# PowerSupply.net
KiCad netlist of a schematic drawn in Altium Designer
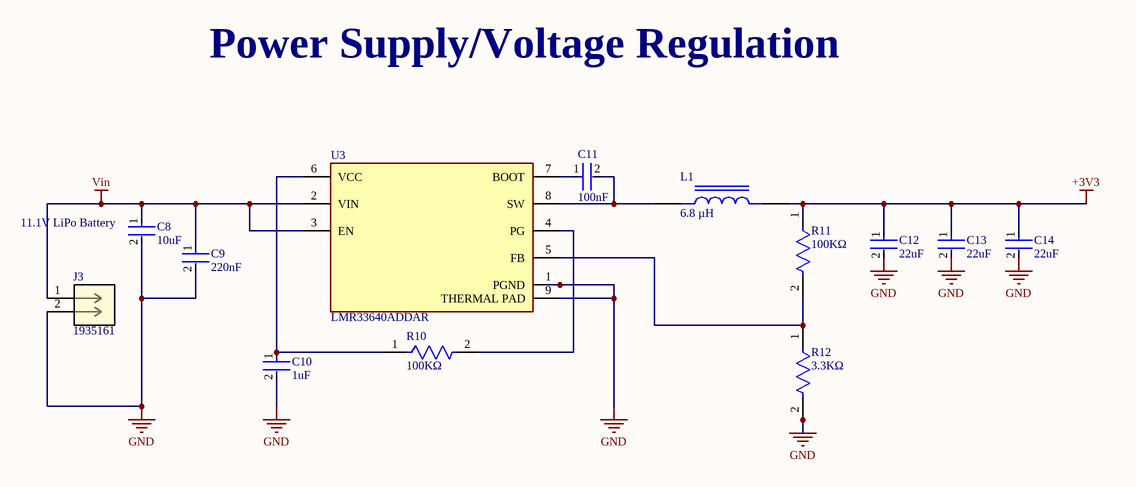
[diagram p0: PowerSupply.SchDoc]

(export (version "E")
  (design (tool "Eeschema 10.0.6"))
  (components
    (comp (ref "C8")
      (value "10uF")
      (footprint "FP-CL21-IPC_A")
      (description "CL21A106KAYNNNE CL21 Series 0805 10uF 25V ±10% Tolerance X5R Multilayer Ceramic Chip Capacitor")
      (fields (field (name "TOLERANCE") "10%"))
      (libsource (lib "Altium Content Vault") (part "b4654b650e69147ec39a6b967a45e02"))
    )
    (comp (ref "C9")
      (value "220nF")
      (footprint "FP-CL21-IPC_B")
      (description "CL21B224KAFNNNE CL21 Series 0805 220nF 25V ±10% Tolerance X7R Multilayer Ceramic Chip Capacitor")
      (fields (field (name "TOLERANCE") "10%"))
      (libsource (lib "Altium Content Vault") (part "b4654b650e69147ec39a6b967a45e02"))
    )
    (comp (ref "C10")
      (value "1uF")
      (footprint "FP-CL10-IPC_C")
      (description "CL10A105KA8NNNC Cap Ceramic 1uF 25V X5R ±10% Pad SMD 0603 +85°C T/R")
      (fields (field (name "VOLTAGE") "25V") (field (name "TOLERANCE") "10%"))
      (libsource (lib "Altium Content Vault") (part "b4654b650e69147ec39a6b967a45e02"))
    )
    (comp (ref "C11")
      (value "100nF")
      (footprint "FP-CL21-IPC_C")
      (description "CL21B104KACNNNC CL21 Series 0805 100nF 25V ±10% Tolerance X7R Multilayer Ceramic Chip Capacitor")
      (fields (field (name "VOLTAGE") "25V") (field (name "TOLERANCE") "10%"))
      (libsource (lib "Altium Content Vault") (part "b4654b650e69147ec39a6b967a45e02"))
    )
    (comp (ref "C12")
      (value "22uF")
      (footprint "FP-CL21-IPC_C")
      (description "CL21A226MAYNNNE CL21 Series 0805 22uF 25V ±20% Tolerance X5R Multilayer Ceramic Chip Capacitor")
      (libsource (lib "Altium Content Vault") (part "b4654b650e69147ec39a6b967a45e02"))
    )
    (comp (ref "C13")
      (value "22uF")
      (footprint "FP-CL21-IPC_C")
      (description "CL21A226MAYNNNE CL21 Series 0805 22uF 25V ±20% Tolerance X5R Multilayer Ceramic Chip Capacitor")
      (libsource (lib "Altium Content Vault") (part "b4654b650e69147ec39a6b967a45e02"))
    )
    (comp (ref "C14")
      (value "22uF")
      (footprint "FP-CL21-IPC_C")
      (description "CL21A226MAYNNNE CL21 Series 0805 22uF 25V ±20% Tolerance X5R Multilayer Ceramic Chip Capacitor")
      (libsource (lib "Altium Content Vault") (part "b4654b650e69147ec39a6b967a45e02"))
    )
    (comp (ref "J3")
      (value "1935161")
      (footprint "CONN_1935161_PXC")
      (fields
        (field (name "MANUFACTURER") "Samsung")
        (field (name "MANUFACTURER PART NUMBER") "CL21A106KOQNNNE")
      )
      (libsource (lib "1935161") (part "1935161"))
    )
    (comp (ref "L1")
      (value "6.8 µH")
      (footprint "IND_SRN8040TA-6R8M:IND_SRN8040TA-6R8M")
      (description "SRN8040TA-6R8M FIXED IND 6.8UH 5.1A 25 MOHM SMD")
      (fields (field (name "MP") "SRN8040TA-6R8M"))
      (libsource (lib "SRN8040TA-6R8M") (part "SRN8040TA-6R8M"))
    )
    (comp (ref "R10")
      (value "100KΩ")
      (footprint "FP-CRGP2512-IPC_C")
      (description "CRGP2512F100K CRGP2512 100KΩ 2W ±100ppm/°C 1% 500V")
      (fields
        (field (name "OCTOPART") "https://octopart.com/crgp2512f100k-te+connectivity-91019024")
        (field (name "MANUFACTURER") "TE")
      )
      (libsource (lib "Altium Content Vault") (part "1029c3af85768c4190bb7ad29bc67b5"))
    )
    (comp (ref "R11")
      (value "100KΩ")
      (footprint "FP-CRGP2512-IPC_C")
      (description "CRGP2512F100K CRGP2512 100KΩ 2W ±100ppm/°C 1% 500V")
      (fields
        (field (name "OCTOPART") "https://octopart.com/crgp2512f100k-te+connectivity-91019024")
        (field (name "MANUFACTURER") "TE")
      )
      (libsource (lib "Altium Content Vault") (part "1029c3af85768c4190bb7ad29bc67b5"))
    )
    (comp (ref "R12")
      (value "3.3KΩ")
      (footprint "FP-CRGP2512-IPC_C")
      (description "CRGP2512F3K3 CRGP2512 3.3KΩ 2W ±100ppm/°C 1% 500V")
      (fields
        (field (name "MANUFACTURER") "TE")
        (field (name "OCTOPART") "https://octopart.com/crgp2512f3k3-te+connectivity-91019064")
      )
      (libsource (lib "Altium Content Vault") (part "1029c3af85768c4190bb7ad29bc67b5"))
    )
    (comp (ref "U3")
      (value "LMR33640ADDAR")
      (footprint "FP-DDA0008J-IPC_A")
      (description "36V 4A 400KHZ REGULATOR")
      (libsource (lib "Altium Content Vault") (part "88f7987fbe75384f65cab7a50dd0ee1"))
    )
  )
  (nets
    (net (code "1") (name "+3V3") (class "Default")
      (node (ref "C12") (pin "1") (pinfunction "1_1") (pintype "passive"))
      (node (ref "C13") (pin "1") (pinfunction "1_1") (pintype "passive"))
      (node (ref "C14") (pin "1") (pinfunction "1_1") (pintype "passive"))
      (node (ref "L1") (pin "2") (pinfunction "2_2") (pintype "passive"))
      (node (ref "R11") (pin "1") (pinfunction "1_1") (pintype "passive"))
    )
    (net (code "2") (name "GND") (class "Default")
      (node (ref "C10") (pin "2") (pinfunction "2_2") (pintype "passive"))
      (node (ref "C12") (pin "2") (pinfunction "2_2") (pintype "passive"))
      (node (ref "C13") (pin "2") (pinfunction "2_2") (pintype "passive"))
      (node (ref "C14") (pin "2") (pinfunction "2_2") (pintype "passive"))
      (node (ref "C8") (pin "2") (pinfunction "2_2") (pintype "passive"))
      (node (ref "C9") (pin "2") (pinfunction "2_2") (pintype "passive"))
      (node (ref "J3") (pin "2") (pinfunction "2_2") (pintype "passive"))
      (node (ref "R12") (pin "2") (pinfunction "2_2") (pintype "passive"))
      (node (ref "U3") (pin "1") (pinfunction "PGND_1") (pintype "power_in"))
      (node (ref "U3") (pin "9") (pinfunction "THERMAL_PAD_9") (pintype "power_in"))
    )
    (net (code "3") (name "Net-(U3-BOOT)") (class "Default")
      (node (ref "C11") (pin "1") (pinfunction "1_1") (pintype "passive"))
      (node (ref "U3") (pin "7") (pinfunction "BOOT_7") (pintype "power_in"))
    )
    (net (code "4") (name "Net-(U3-FB)") (class "Default")
      (node (ref "R11") (pin "2") (pinfunction "2_2") (pintype "passive"))
      (node (ref "R12") (pin "1") (pinfunction "1_1") (pintype "passive"))
      (node (ref "U3") (pin "5") (pinfunction "FB_5") (pintype "passive"))
    )
    (net (code "5") (name "Net-(U3-PG)") (class "Default")
      (node (ref "R10") (pin "2") (pinfunction "2_2") (pintype "passive"))
      (node (ref "U3") (pin "4") (pinfunction "PG_4") (pintype "passive"))
    )
    (net (code "6") (name "Net-(U3-SW)") (class "Default")
      (node (ref "C11") (pin "2") (pinfunction "2_2") (pintype "passive"))
      (node (ref "L1") (pin "1") (pinfunction "1_1") (pintype "passive"))
      (node (ref "U3") (pin "8") (pinfunction "SW_8") (pintype "power_in"))
    )
    (net (code "7") (name "Net-(U3-VCC)") (class "Default")
      (node (ref "C10") (pin "1") (pinfunction "1_1") (pintype "passive"))
      (node (ref "R10") (pin "1") (pinfunction "1_1") (pintype "passive"))
      (node (ref "U3") (pin "6") (pinfunction "VCC_6") (pintype "power_in"))
    )
    (net (code "8") (name "Vin") (class "Default")
      (node (ref "C8") (pin "1") (pinfunction "1_1") (pintype "passive"))
      (node (ref "C9") (pin "1") (pinfunction "1_1") (pintype "passive"))
      (node (ref "J3") (pin "1") (pinfunction "1_1") (pintype "passive"))
      (node (ref "U3") (pin "2") (pinfunction "VIN_2") (pintype "power_in"))
      (node (ref "U3") (pin "3") (pinfunction "EN_3") (pintype "passive"))
    )
  )
)
